# Ethernet_Con_Demo.net
KiCad netlist of a schematic drawn in Altium Designer
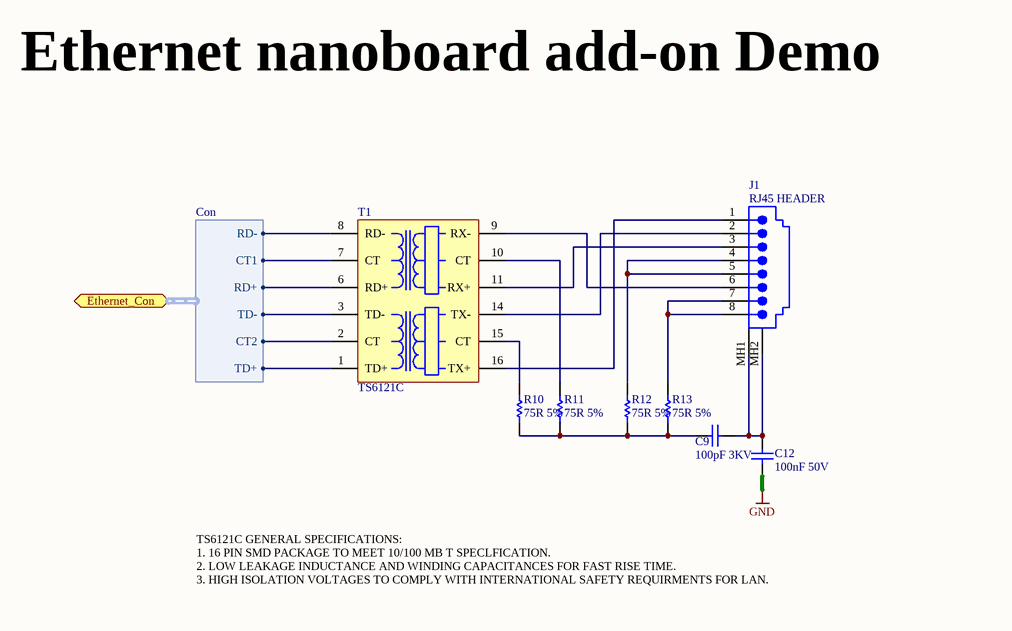
[diagram p0: Ethernet_Con_Demo.SchDoc]

(export (version "E")
  (design (tool "Eeschema 10.0.6"))
  (components
    (comp (ref "C9")
      (value "100pF 3KV")
      (footprint "PHY_Demo:CAPR7_5-3_6x7_5")
      (description "Capacitor")
      (libsource (lib "Altium Design Library") (part "CAP-NP"))
    )
    (comp (ref "C12")
      (value "100nF 50V")
      (footprint "PHY_Demo:CAPC2012")
      (description "Capacitor")
      (libsource (lib "Altium Design Library") (part "CAP-NP"))
    )
    (comp (ref "J1")
      (value "RJ45 HEADER")
      (footprint "PHY_Demo:95122-2881")
      (description "Right Angle, Standard Profile, External Shield PCB Jack")
      (libsource (lib "Altium Design Library") (part "CON-RJ45-10-RA"))
    )
    (comp (ref "R10")
      (value "75R 5%")
      (footprint "PHY_Demo:RESC2012")
      (description "Resistor")
      (libsource (lib "Altium Design Library") (part "RES"))
    )
    (comp (ref "R11")
      (value "75R 5%")
      (footprint "PHY_Demo:RESC2012")
      (description "Resistor")
      (libsource (lib "Altium Design Library") (part "RES"))
    )
    (comp (ref "R12")
      (value "75R 5%")
      (footprint "PHY_Demo:RESC2012")
      (description "Resistor")
      (libsource (lib "Altium Design Library") (part "RES"))
    )
    (comp (ref "R13")
      (value "75R 5%")
      (footprint "PHY_Demo:RESC2012")
      (description "Resistor")
      (libsource (lib "Altium Design Library") (part "RES"))
    )
    (comp (ref "T1")
      (value "TS6121C")
      (footprint "PHY_Demo:SOIC127P910-16")
      (description "Bothhand 10/100 BaseT Pulse Transformer")
      (libsource (lib "Altium Design Library") (part "TS6121C"))
    )
  )
  (nets
    (net (code "2") (name "/CT1") (class "Default")
      (node (ref "T1") (pin "7") (pinfunction "CT_7") (pintype "passive"))
    )
    (net (code "3") (name "/CT2") (class "Default")
      (node (ref "T1") (pin "2") (pinfunction "CT_2") (pintype "passive"))
    )
    (net (code "4") (name "/RD+") (class "Default")
      (node (ref "T1") (pin "6") (pinfunction "RD+_6") (pintype "passive"))
    )
    (net (code "5") (name "/RD-") (class "Default")
      (node (ref "T1") (pin "8") (pinfunction "RD-_8") (pintype "passive"))
    )
    (net (code "6") (name "/TD+") (class "Default")
      (node (ref "T1") (pin "1") (pinfunction "TD+_1") (pintype "passive"))
    )
    (net (code "7") (name "/TD-") (class "Default")
      (node (ref "T1") (pin "3") (pinfunction "TD-_3") (pintype "passive"))
    )
    (net (code "9") (name "GND") (class "Default")
      (node (ref "C12") (pin "1") (pinfunction "1_1") (pintype "passive"))
    )
    (net (code "10") (name "Net-(C9-Pad1)") (class "Default")
      (node (ref "C9") (pin "1") (pinfunction "1_1") (pintype "passive"))
      (node (ref "R10") (pin "1") (pinfunction "1_1") (pintype "passive"))
      (node (ref "R11") (pin "1") (pinfunction "1_1") (pintype "passive"))
      (node (ref "R12") (pin "1") (pinfunction "1_1") (pintype "passive"))
      (node (ref "R13") (pin "1") (pinfunction "1_1") (pintype "passive"))
    )
    (net (code "11") (name "Net-(C12-Pad2)") (class "Default")
      (node (ref "C12") (pin "2") (pinfunction "2_2") (pintype "passive"))
      (node (ref "C9") (pin "2") (pinfunction "2_2") (pintype "passive"))
      (node (ref "J1") (pin "MH1") (pinfunction "Shield_MH1") (pintype "passive"))
      (node (ref "J1") (pin "MH2") (pinfunction "Shield_MH2") (pintype "passive"))
    )
    (net (code "12") (name "Net-(J1-Pad4)") (class "Default")
      (node (ref "J1") (pin "4") (pinfunction "4_4") (pintype "passive"))
      (node (ref "J1") (pin "5") (pinfunction "5_5") (pintype "passive"))
      (node (ref "R12") (pin "2") (pinfunction "2_2") (pintype "passive"))
    )
    (net (code "13") (name "Net-(J1-Pad7)") (class "Default")
      (node (ref "J1") (pin "7") (pinfunction "7_7") (pintype "passive"))
      (node (ref "J1") (pin "8") (pinfunction "8_8") (pintype "passive"))
      (node (ref "R13") (pin "2") (pinfunction "2_2") (pintype "passive"))
    )
    (net (code "14") (name "Net-(R10-Pad2)") (class "Default")
      (node (ref "R10") (pin "2") (pinfunction "2_2") (pintype "passive"))
      (node (ref "T1") (pin "15") (pinfunction "CT_15") (pintype "passive"))
    )
    (net (code "15") (name "Net-(R11-Pad2)") (class "Default")
      (node (ref "R11") (pin "2") (pinfunction "2_2") (pintype "passive"))
      (node (ref "T1") (pin "10") (pinfunction "CT_10") (pintype "passive"))
    )
    (net (code "16") (name "Net-(T1-RX+)") (class "Default")
      (node (ref "J1") (pin "3") (pinfunction "3_3") (pintype "passive"))
      (node (ref "T1") (pin "11") (pinfunction "RX+_11") (pintype "passive"))
    )
    (net (code "17") (name "Net-(T1-RX-)") (class "Default")
      (node (ref "J1") (pin "6") (pinfunction "6_6") (pintype "passive"))
      (node (ref "T1") (pin "9") (pinfunction "RX-_9") (pintype "passive"))
    )
    (net (code "18") (name "Net-(T1-TX+)") (class "Default")
      (node (ref "J1") (pin "1") (pinfunction "1_1") (pintype "passive"))
      (node (ref "T1") (pin "16") (pinfunction "TX+_16") (pintype "passive"))
    )
    (net (code "19") (name "Net-(T1-TX-)") (class "Default")
      (node (ref "J1") (pin "2") (pinfunction "2_2") (pintype "passive"))
      (node (ref "T1") (pin "14") (pinfunction "TX-_14") (pintype "passive"))
    )
  )
)
